# Q24_BRAKE_LIGHT.net
KiCad netlist of a schematic drawn in Altium Designer
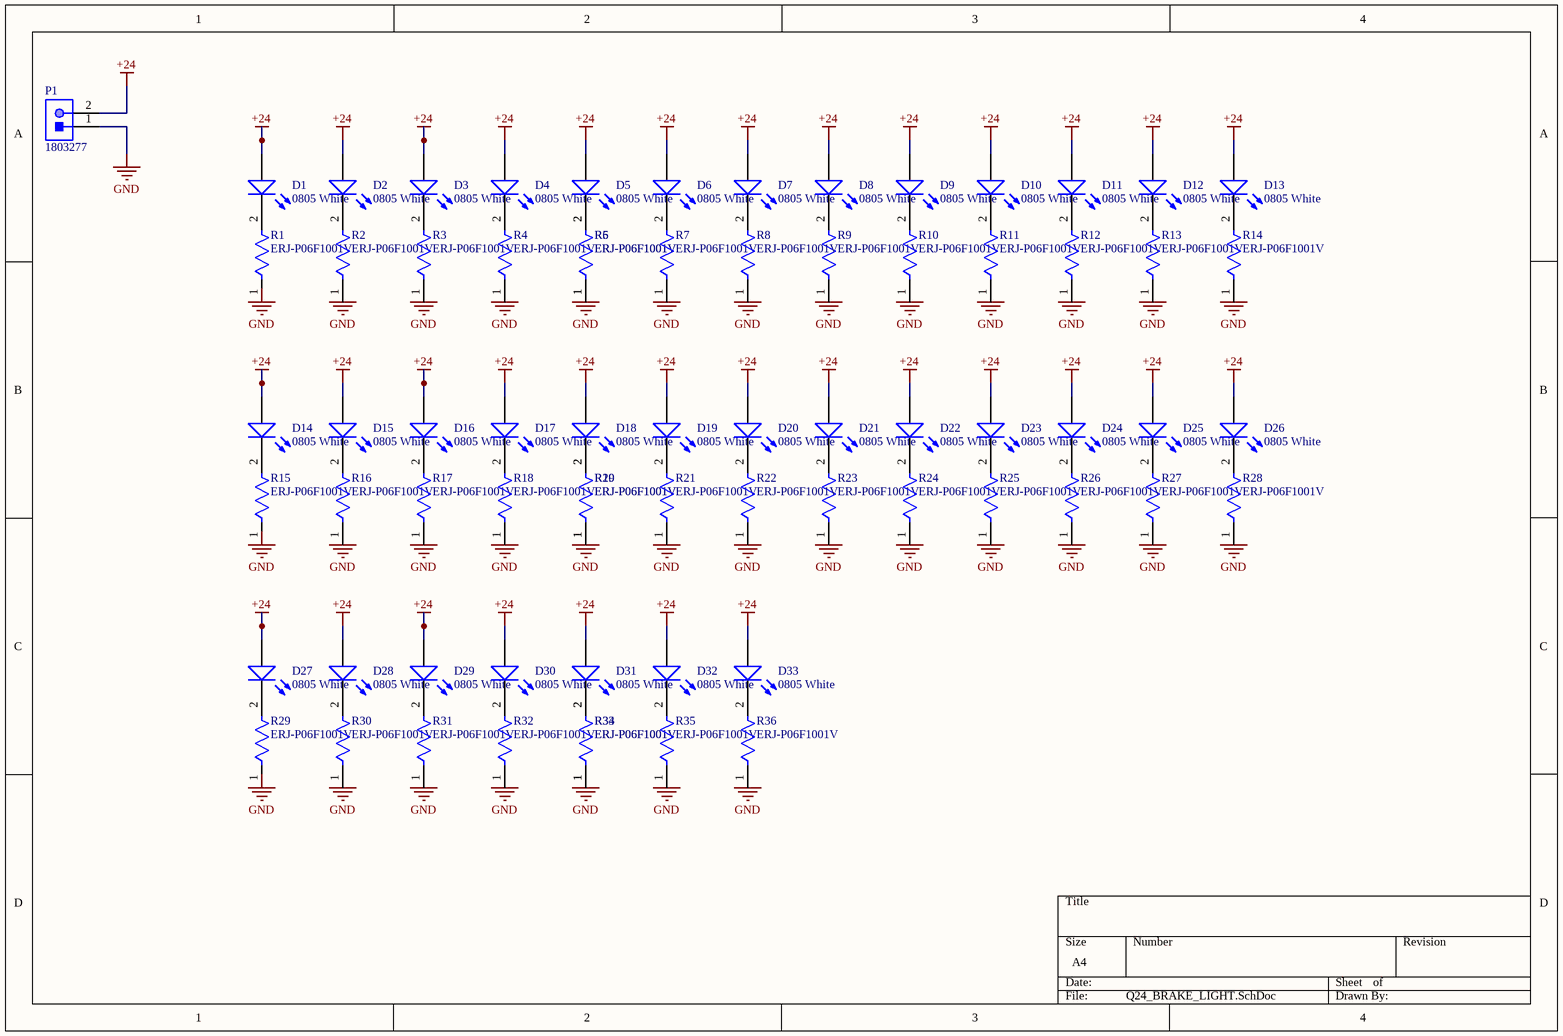
[diagram p0: Q24_BRAKE_LIGHT.SchDoc]

(export (version "E")
  (design (tool "Eeschema 10.0.6"))
  (components
    (comp (ref "D1")
      (value "0805 White")
      (footprint "0805_LED_S1")
      (description "LED")
      (libsource (lib "LED") (part "0805 LED White"))
    )
    (comp (ref "D2")
      (value "0805 White")
      (footprint "0805_LED_S1")
      (description "LED")
      (libsource (lib "LED") (part "0805 LED White"))
    )
    (comp (ref "D3")
      (value "0805 White")
      (footprint "0805_LED_S1")
      (description "LED")
      (libsource (lib "LED") (part "0805 LED White"))
    )
    (comp (ref "D4")
      (value "0805 White")
      (footprint "0805_LED_S1")
      (description "LED")
      (libsource (lib "LED") (part "0805 LED White"))
    )
    (comp (ref "D5")
      (value "0805 White")
      (footprint "0805_LED_S1")
      (description "LED")
      (libsource (lib "LED") (part "0805 LED White"))
    )
    (comp (ref "D6")
      (value "0805 White")
      (footprint "0805_LED_S1")
      (description "LED")
      (libsource (lib "LED") (part "0805 LED White"))
    )
    (comp (ref "D7")
      (value "0805 White")
      (footprint "0805_LED_S1")
      (description "LED")
      (libsource (lib "LED") (part "0805 LED White"))
    )
    (comp (ref "D8")
      (value "0805 White")
      (footprint "0805_LED_S1")
      (description "LED")
      (libsource (lib "LED") (part "0805 LED White"))
    )
    (comp (ref "D9")
      (value "0805 White")
      (footprint "0805_LED_S1")
      (description "LED")
      (libsource (lib "LED") (part "0805 LED White"))
    )
    (comp (ref "D10")
      (value "0805 White")
      (footprint "0805_LED_S1")
      (description "LED")
      (libsource (lib "LED") (part "0805 LED White"))
    )
    (comp (ref "D11")
      (value "0805 White")
      (footprint "0805_LED_S1")
      (description "LED")
      (libsource (lib "LED") (part "0805 LED White"))
    )
    (comp (ref "D12")
      (value "0805 White")
      (footprint "0805_LED_S1")
      (description "LED")
      (libsource (lib "LED") (part "0805 LED White"))
    )
    (comp (ref "D13")
      (value "0805 White")
      (footprint "0805_LED_S1")
      (description "LED")
      (libsource (lib "LED") (part "0805 LED White"))
    )
    (comp (ref "D14")
      (value "0805 White")
      (footprint "0805_LED_S1")
      (description "LED")
      (libsource (lib "LED") (part "0805 LED White"))
    )
    (comp (ref "D15")
      (value "0805 White")
      (footprint "0805_LED_S1")
      (description "LED")
      (libsource (lib "LED") (part "0805 LED White"))
    )
    (comp (ref "D16")
      (value "0805 White")
      (footprint "0805_LED_S1")
      (description "LED")
      (libsource (lib "LED") (part "0805 LED White"))
    )
    (comp (ref "D17")
      (value "0805 White")
      (footprint "0805_LED_S1")
      (description "LED")
      (libsource (lib "LED") (part "0805 LED White"))
    )
    (comp (ref "D18")
      (value "0805 White")
      (footprint "0805_LED_S1")
      (description "LED")
      (libsource (lib "LED") (part "0805 LED White"))
    )
    (comp (ref "D19")
      (value "0805 White")
      (footprint "0805_LED_S1")
      (description "LED")
      (libsource (lib "LED") (part "0805 LED White"))
    )
    (comp (ref "D20")
      (value "0805 White")
      (footprint "0805_LED_S1")
      (description "LED")
      (libsource (lib "LED") (part "0805 LED White"))
    )
    (comp (ref "D21")
      (value "0805 White")
      (footprint "0805_LED_S1")
      (description "LED")
      (libsource (lib "LED") (part "0805 LED White"))
    )
    (comp (ref "D22")
      (value "0805 White")
      (footprint "0805_LED_S1")
      (description "LED")
      (libsource (lib "LED") (part "0805 LED White"))
    )
    (comp (ref "D23")
      (value "0805 White")
      (footprint "0805_LED_S1")
      (description "LED")
      (libsource (lib "LED") (part "0805 LED White"))
    )
    (comp (ref "D24")
      (value "0805 White")
      (footprint "0805_LED_S1")
      (description "LED")
      (libsource (lib "LED") (part "0805 LED White"))
    )
    (comp (ref "D25")
      (value "0805 White")
      (footprint "0805_LED_S1")
      (description "LED")
      (libsource (lib "LED") (part "0805 LED White"))
    )
    (comp (ref "D26")
      (value "0805 White")
      (footprint "0805_LED_S1")
      (description "LED")
      (libsource (lib "LED") (part "0805 LED White"))
    )
    (comp (ref "D27")
      (value "0805 White")
      (footprint "0805_LED_S1")
      (description "LED")
      (libsource (lib "LED") (part "0805 LED White"))
    )
    (comp (ref "D28")
      (value "0805 White")
      (footprint "0805_LED_S1")
      (description "LED")
      (libsource (lib "LED") (part "0805 LED White"))
    )
    (comp (ref "D29")
      (value "0805 White")
      (footprint "0805_LED_S1")
      (description "LED")
      (libsource (lib "LED") (part "0805 LED White"))
    )
    (comp (ref "D30")
      (value "0805 White")
      (footprint "0805_LED_S1")
      (description "LED")
      (libsource (lib "LED") (part "0805 LED White"))
    )
    (comp (ref "D31")
      (value "0805 White")
      (footprint "0805_LED_S1")
      (description "LED")
      (libsource (lib "LED") (part "0805 LED White"))
    )
    (comp (ref "D32")
      (value "0805 White")
      (footprint "0805_LED_S1")
      (description "LED")
      (libsource (lib "LED") (part "0805 LED White"))
    )
    (comp (ref "D33")
      (value "0805 White")
      (footprint "0805_LED_S1")
      (description "LED")
      (libsource (lib "LED") (part "0805 LED White"))
    )
    (comp (ref "P1")
      (value "1803277")
      (footprint "PHOE-1803277_V")
      (description "Male Header, Pitch 3.81 mm, 1 x 2 Position, Height 7.25 mm, Tail Length 3.4 mm, RoHS, Bulk")
      (fields (field (name "MANUFACTURER") "Phoenix Contact"))
      (libsource (lib "Americas- FSAE- Queens University") (part "CN-1P-M-R2"))
    )
    (comp (ref "R1")
      (value "ERJ-P06F1001V")
      (footprint "FP-ERJP06-IPC_C")
      (description "RES SMD 1K OHM 1% 1/2W 0805")
      (fields (field (name "TOLERANCE") "1%"))
      (libsource (lib "Altium Content Vault") (part "1029c3af85768c4190bb7ad29bc67b5"))
    )
    (comp (ref "R2")
      (value "ERJ-P06F1001V")
      (footprint "FP-ERJP06-IPC_C")
      (description "RES SMD 1K OHM 1% 1/2W 0805")
      (fields (field (name "TOLERANCE") "1%"))
      (libsource (lib "Altium Content Vault") (part "1029c3af85768c4190bb7ad29bc67b5"))
    )
    (comp (ref "R3")
      (value "ERJ-P06F1001V")
      (footprint "FP-ERJP06-IPC_C")
      (description "RES SMD 1K OHM 1% 1/2W 0805")
      (fields (field (name "TOLERANCE") "1%"))
      (libsource (lib "Altium Content Vault") (part "1029c3af85768c4190bb7ad29bc67b5"))
    )
    (comp (ref "R4")
      (value "ERJ-P06F1001V")
      (footprint "FP-ERJP06-IPC_C")
      (description "RES SMD 1K OHM 1% 1/2W 0805")
      (fields (field (name "TOLERANCE") "1%"))
      (libsource (lib "Altium Content Vault") (part "1029c3af85768c4190bb7ad29bc67b5"))
    )
    (comp (ref "R5")
      (value "ERJ-P06F1001V")
      (footprint "FP-ERJP06-IPC_C")
      (description "RES SMD 1K OHM 1% 1/2W 0805")
      (fields (field (name "TOLERANCE") "1%"))
      (libsource (lib "Altium Content Vault") (part "1029c3af85768c4190bb7ad29bc67b5"))
    )
    (comp (ref "R6")
      (value "ERJ-P06F1001V")
      (footprint "FP-ERJP06-IPC_C")
      (description "RES SMD 1K OHM 1% 1/2W 0805")
      (fields (field (name "TOLERANCE") "1%"))
      (libsource (lib "Altium Content Vault") (part "1029c3af85768c4190bb7ad29bc67b5"))
    )
    (comp (ref "R7")
      (value "ERJ-P06F1001V")
      (footprint "FP-ERJP06-IPC_C")
      (description "RES SMD 1K OHM 1% 1/2W 0805")
      (fields (field (name "TOLERANCE") "1%"))
      (libsource (lib "Altium Content Vault") (part "1029c3af85768c4190bb7ad29bc67b5"))
    )
    (comp (ref "R8")
      (value "ERJ-P06F1001V")
      (footprint "FP-ERJP06-IPC_C")
      (description "RES SMD 1K OHM 1% 1/2W 0805")
      (fields (field (name "TOLERANCE") "1%"))
      (libsource (lib "Altium Content Vault") (part "1029c3af85768c4190bb7ad29bc67b5"))
    )
    (comp (ref "R9")
      (value "ERJ-P06F1001V")
      (footprint "FP-ERJP06-IPC_C")
      (description "RES SMD 1K OHM 1% 1/2W 0805")
      (fields (field (name "TOLERANCE") "1%"))
      (libsource (lib "Altium Content Vault") (part "1029c3af85768c4190bb7ad29bc67b5"))
    )
    (comp (ref "R10")
      (value "ERJ-P06F1001V")
      (footprint "FP-ERJP06-IPC_C")
      (description "RES SMD 1K OHM 1% 1/2W 0805")
      (fields (field (name "TOLERANCE") "1%"))
      (libsource (lib "Altium Content Vault") (part "1029c3af85768c4190bb7ad29bc67b5"))
    )
    (comp (ref "R11")
      (value "ERJ-P06F1001V")
      (footprint "FP-ERJP06-IPC_C")
      (description "RES SMD 1K OHM 1% 1/2W 0805")
      (fields (field (name "TOLERANCE") "1%"))
      (libsource (lib "Altium Content Vault") (part "1029c3af85768c4190bb7ad29bc67b5"))
    )
    (comp (ref "R12")
      (value "ERJ-P06F1001V")
      (footprint "FP-ERJP06-IPC_C")
      (description "RES SMD 1K OHM 1% 1/2W 0805")
      (fields (field (name "TOLERANCE") "1%"))
      (libsource (lib "Altium Content Vault") (part "1029c3af85768c4190bb7ad29bc67b5"))
    )
    (comp (ref "R13")
      (value "ERJ-P06F1001V")
      (footprint "FP-ERJP06-IPC_C")
      (description "RES SMD 1K OHM 1% 1/2W 0805")
      (fields (field (name "TOLERANCE") "1%"))
      (libsource (lib "Altium Content Vault") (part "1029c3af85768c4190bb7ad29bc67b5"))
    )
    (comp (ref "R14")
      (value "ERJ-P06F1001V")
      (footprint "FP-ERJP06-IPC_C")
      (description "RES SMD 1K OHM 1% 1/2W 0805")
      (fields (field (name "TOLERANCE") "1%"))
      (libsource (lib "Altium Content Vault") (part "1029c3af85768c4190bb7ad29bc67b5"))
    )
    (comp (ref "R15")
      (value "ERJ-P06F1001V")
      (footprint "FP-ERJP06-IPC_C")
      (description "RES SMD 1K OHM 1% 1/2W 0805")
      (fields (field (name "TOLERANCE") "1%"))
      (libsource (lib "Altium Content Vault") (part "1029c3af85768c4190bb7ad29bc67b5"))
    )
    (comp (ref "R16")
      (value "ERJ-P06F1001V")
      (footprint "FP-ERJP06-IPC_C")
      (description "RES SMD 1K OHM 1% 1/2W 0805")
      (fields (field (name "TOLERANCE") "1%"))
      (libsource (lib "Altium Content Vault") (part "1029c3af85768c4190bb7ad29bc67b5"))
    )
    (comp (ref "R17")
      (value "ERJ-P06F1001V")
      (footprint "FP-ERJP06-IPC_C")
      (description "RES SMD 1K OHM 1% 1/2W 0805")
      (fields (field (name "TOLERANCE") "1%"))
      (libsource (lib "Altium Content Vault") (part "1029c3af85768c4190bb7ad29bc67b5"))
    )
    (comp (ref "R18")
      (value "ERJ-P06F1001V")
      (footprint "FP-ERJP06-IPC_C")
      (description "RES SMD 1K OHM 1% 1/2W 0805")
      (fields (field (name "TOLERANCE") "1%"))
      (libsource (lib "Altium Content Vault") (part "1029c3af85768c4190bb7ad29bc67b5"))
    )
    (comp (ref "R19")
      (value "ERJ-P06F1001V")
      (footprint "FP-ERJP06-IPC_C")
      (description "RES SMD 1K OHM 1% 1/2W 0805")
      (fields (field (name "TOLERANCE") "1%"))
      (libsource (lib "Altium Content Vault") (part "1029c3af85768c4190bb7ad29bc67b5"))
    )
    (comp (ref "R20")
      (value "ERJ-P06F1001V")
      (footprint "FP-ERJP06-IPC_C")
      (description "RES SMD 1K OHM 1% 1/2W 0805")
      (fields (field (name "TOLERANCE") "1%"))
      (libsource (lib "Altium Content Vault") (part "1029c3af85768c4190bb7ad29bc67b5"))
    )
    (comp (ref "R21")
      (value "ERJ-P06F1001V")
      (footprint "FP-ERJP06-IPC_C")
      (description "RES SMD 1K OHM 1% 1/2W 0805")
      (fields (field (name "TOLERANCE") "1%"))
      (libsource (lib "Altium Content Vault") (part "1029c3af85768c4190bb7ad29bc67b5"))
    )
    (comp (ref "R22")
      (value "ERJ-P06F1001V")
      (footprint "FP-ERJP06-IPC_C")
      (description "RES SMD 1K OHM 1% 1/2W 0805")
      (fields (field (name "TOLERANCE") "1%"))
      (libsource (lib "Altium Content Vault") (part "1029c3af85768c4190bb7ad29bc67b5"))
    )
    (comp (ref "R23")
      (value "ERJ-P06F1001V")
      (footprint "FP-ERJP06-IPC_C")
      (description "RES SMD 1K OHM 1% 1/2W 0805")
      (fields (field (name "TOLERANCE") "1%"))
      (libsource (lib "Altium Content Vault") (part "1029c3af85768c4190bb7ad29bc67b5"))
    )
    (comp (ref "R24")
      (value "ERJ-P06F1001V")
      (footprint "FP-ERJP06-IPC_C")
      (description "RES SMD 1K OHM 1% 1/2W 0805")
      (fields (field (name "TOLERANCE") "1%"))
      (libsource (lib "Altium Content Vault") (part "1029c3af85768c4190bb7ad29bc67b5"))
    )
    (comp (ref "R25")
      (value "ERJ-P06F1001V")
      (footprint "FP-ERJP06-IPC_C")
      (description "RES SMD 1K OHM 1% 1/2W 0805")
      (fields (field (name "TOLERANCE") "1%"))
      (libsource (lib "Altium Content Vault") (part "1029c3af85768c4190bb7ad29bc67b5"))
    )
    (comp (ref "R26")
      (value "ERJ-P06F1001V")
      (footprint "FP-ERJP06-IPC_C")
      (description "RES SMD 1K OHM 1% 1/2W 0805")
      (fields (field (name "TOLERANCE") "1%"))
      (libsource (lib "Altium Content Vault") (part "1029c3af85768c4190bb7ad29bc67b5"))
    )
    (comp (ref "R27")
      (value "ERJ-P06F1001V")
      (footprint "FP-ERJP06-IPC_C")
      (description "RES SMD 1K OHM 1% 1/2W 0805")
      (fields (field (name "TOLERANCE") "1%"))
      (libsource (lib "Altium Content Vault") (part "1029c3af85768c4190bb7ad29bc67b5"))
    )
    (comp (ref "R28")
      (value "ERJ-P06F1001V")
      (footprint "FP-ERJP06-IPC_C")
      (description "RES SMD 1K OHM 1% 1/2W 0805")
      (fields (field (name "TOLERANCE") "1%"))
      (libsource (lib "Altium Content Vault") (part "1029c3af85768c4190bb7ad29bc67b5"))
    )
    (comp (ref "R29")
      (value "ERJ-P06F1001V")
      (footprint "FP-ERJP06-IPC_C")
      (description "RES SMD 1K OHM 1% 1/2W 0805")
      (fields (field (name "TOLERANCE") "1%"))
      (libsource (lib "Altium Content Vault") (part "1029c3af85768c4190bb7ad29bc67b5"))
    )
    (comp (ref "R30")
      (value "ERJ-P06F1001V")
      (footprint "FP-ERJP06-IPC_C")
      (description "RES SMD 1K OHM 1% 1/2W 0805")
      (fields (field (name "TOLERANCE") "1%"))
      (libsource (lib "Altium Content Vault") (part "1029c3af85768c4190bb7ad29bc67b5"))
    )
    (comp (ref "R31")
      (value "ERJ-P06F1001V")
      (footprint "FP-ERJP06-IPC_C")
      (description "RES SMD 1K OHM 1% 1/2W 0805")
      (fields (field (name "TOLERANCE") "1%"))
      (libsource (lib "Altium Content Vault") (part "1029c3af85768c4190bb7ad29bc67b5"))
    )
    (comp (ref "R32")
      (value "ERJ-P06F1001V")
      (footprint "FP-ERJP06-IPC_C")
      (description "RES SMD 1K OHM 1% 1/2W 0805")
      (fields (field (name "TOLERANCE") "1%"))
      (libsource (lib "Altium Content Vault") (part "1029c3af85768c4190bb7ad29bc67b5"))
    )
    (comp (ref "R33")
      (value "ERJ-P06F1001V")
      (footprint "FP-ERJP06-IPC_C")
      (description "RES SMD 1K OHM 1% 1/2W 0805")
      (fields (field (name "TOLERANCE") "1%"))
      (libsource (lib "Altium Content Vault") (part "1029c3af85768c4190bb7ad29bc67b5"))
    )
    (comp (ref "R34")
      (value "ERJ-P06F1001V")
      (footprint "FP-ERJP06-IPC_C")
      (description "RES SMD 1K OHM 1% 1/2W 0805")
      (fields (field (name "TOLERANCE") "1%"))
      (libsource (lib "Altium Content Vault") (part "1029c3af85768c4190bb7ad29bc67b5"))
    )
    (comp (ref "R35")
      (value "ERJ-P06F1001V")
      (footprint "FP-ERJP06-IPC_C")
      (description "RES SMD 1K OHM 1% 1/2W 0805")
      (fields (field (name "TOLERANCE") "1%"))
      (libsource (lib "Altium Content Vault") (part "1029c3af85768c4190bb7ad29bc67b5"))
    )
    (comp (ref "R36")
      (value "ERJ-P06F1001V")
      (footprint "FP-ERJP06-IPC_C")
      (description "RES SMD 1K OHM 1% 1/2W 0805")
      (fields (field (name "TOLERANCE") "1%"))
      (libsource (lib "Altium Content Vault") (part "1029c3af85768c4190bb7ad29bc67b5"))
    )
  )
  (nets
    (net (code "1") (name "+24") (class "Default")
      (node (ref "D1") (pin "A") (pinfunction "A_A") (pintype "passive"))
      (node (ref "D10") (pin "A") (pinfunction "A_A") (pintype "passive"))
      (node (ref "D11") (pin "A") (pinfunction "A_A") (pintype "passive"))
      (node (ref "D12") (pin "A") (pinfunction "A_A") (pintype "passive"))
      (node (ref "D13") (pin "A") (pinfunction "A_A") (pintype "passive"))
      (node (ref "D14") (pin "A") (pinfunction "A_A") (pintype "passive"))
      (node (ref "D15") (pin "A") (pinfunction "A_A") (pintype "passive"))
      (node (ref "D16") (pin "A") (pinfunction "A_A") (pintype "passive"))
      (node (ref "D17") (pin "A") (pinfunction "A_A") (pintype "passive"))
      (node (ref "D18") (pin "A") (pinfunction "A_A") (pintype "passive"))
      (node (ref "D19") (pin "A") (pinfunction "A_A") (pintype "passive"))
      (node (ref "D2") (pin "A") (pinfunction "A_A") (pintype "passive"))
      (node (ref "D20") (pin "A") (pinfunction "A_A") (pintype "passive"))
      (node (ref "D21") (pin "A") (pinfunction "A_A") (pintype "passive"))
      (node (ref "D22") (pin "A") (pinfunction "A_A") (pintype "passive"))
      (node (ref "D23") (pin "A") (pinfunction "A_A") (pintype "passive"))
      (node (ref "D24") (pin "A") (pinfunction "A_A") (pintype "passive"))
      (node (ref "D25") (pin "A") (pinfunction "A_A") (pintype "passive"))
      (node (ref "D26") (pin "A") (pinfunction "A_A") (pintype "passive"))
      (node (ref "D27") (pin "A") (pinfunction "A_A") (pintype "passive"))
      (node (ref "D28") (pin "A") (pinfunction "A_A") (pintype "passive"))
      (node (ref "D29") (pin "A") (pinfunction "A_A") (pintype "passive"))
      (node (ref "D3") (pin "A") (pinfunction "A_A") (pintype "passive"))
      (node (ref "D30") (pin "A") (pinfunction "A_A") (pintype "passive"))
      (node (ref "D31") (pin "A") (pinfunction "A_A") (pintype "passive"))
      (node (ref "D32") (pin "A") (pinfunction "A_A") (pintype "passive"))
      (node (ref "D33") (pin "A") (pinfunction "A_A") (pintype "passive"))
      (node (ref "D4") (pin "A") (pinfunction "A_A") (pintype "passive"))
      (node (ref "D5") (pin "A") (pinfunction "A_A") (pintype "passive"))
      (node (ref "D6") (pin "A") (pinfunction "A_A") (pintype "passive"))
      (node (ref "D7") (pin "A") (pinfunction "A_A") (pintype "passive"))
      (node (ref "D8") (pin "A") (pinfunction "A_A") (pintype "passive"))
      (node (ref "D9") (pin "A") (pinfunction "A_A") (pintype "passive"))
      (node (ref "P1") (pin "2") (pinfunction "2_2") (pintype "passive"))
    )
    (net (code "2") (name "GND") (class "Default")
      (node (ref "P1") (pin "1") (pinfunction "1_1") (pintype "passive"))
    )
    (net (code "3") (name "Net-(R5-Pad1)") (class "Default")
      (node (ref "R5") (pin "1") (pinfunction "1_1") (pintype "passive"))
      (node (ref "R6") (pin "1") (pinfunction "1_1") (pintype "passive"))
    )
    (net (code "4") (name "Net-(R5-Pad2)") (class "Default")
      (node (ref "R5") (pin "2") (pinfunction "2_2") (pintype "passive"))
      (node (ref "R6") (pin "2") (pinfunction "2_2") (pintype "passive"))
    )
    (net (code "5") (name "Net-(R19-Pad1)") (class "Default")
      (node (ref "R19") (pin "1") (pinfunction "1_1") (pintype "passive"))
      (node (ref "R20") (pin "1") (pinfunction "1_1") (pintype "passive"))
    )
    (net (code "6") (name "Net-(R19-Pad2)") (class "Default")
      (node (ref "R19") (pin "2") (pinfunction "2_2") (pintype "passive"))
      (node (ref "R20") (pin "2") (pinfunction "2_2") (pintype "passive"))
    )
    (net (code "7") (name "Net-(R33-Pad1)") (class "Default")
      (node (ref "R33") (pin "1") (pinfunction "1_1") (pintype "passive"))
      (node (ref "R34") (pin "1") (pinfunction "1_1") (pintype "passive"))
    )
    (net (code "8") (name "Net-(R33-Pad2)") (class "Default")
      (node (ref "R33") (pin "2") (pinfunction "2_2") (pintype "passive"))
      (node (ref "R34") (pin "2") (pinfunction "2_2") (pintype "passive"))
    )
    (net (code "9") (name "unconnected-(D1-PadK)") (class "Default")
      (node (ref "D1") (pin "K") (pinfunction "K_K") (pintype "passive"))
    )
    (net (code "10") (name "unconnected-(D2-PadK)") (class "Default")
      (node (ref "D2") (pin "K") (pinfunction "K_K") (pintype "passive"))
    )
    (net (code "11") (name "unconnected-(D3-PadK)") (class "Default")
      (node (ref "D3") (pin "K") (pinfunction "K_K") (pintype "passive"))
    )
    (net (code "12") (name "unconnected-(D4-PadK)") (class "Default")
      (node (ref "D4") (pin "K") (pinfunction "K_K") (pintype "passive"))
    )
    (net (code "13") (name "unconnected-(D5-PadK)") (class "Default")
      (node (ref "D5") (pin "K") (pinfunction "K_K") (pintype "passive"))
    )
    (net (code "14") (name "unconnected-(D6-PadK)") (class "Default")
      (node (ref "D6") (pin "K") (pinfunction "K_K") (pintype "passive"))
    )
    (net (code "15") (name "unconnected-(D7-PadK)") (class "Default")
      (node (ref "D7") (pin "K") (pinfunction "K_K") (pintype "passive"))
    )
    (net (code "16") (name "unconnected-(D8-PadK)") (class "Default")
      (node (ref "D8") (pin "K") (pinfunction "K_K") (pintype "passive"))
    )
    (net (code "17") (name "unconnected-(D9-PadK)") (class "Default")
      (node (ref "D9") (pin "K") (pinfunction "K_K") (pintype "passive"))
    )
    (net (code "18") (name "unconnected-(D10-PadK)") (class "Default")
      (node (ref "D10") (pin "K") (pinfunction "K_K") (pintype "passive"))
    )
    (net (code "19") (name "unconnected-(D11-PadK)") (class "Default")
      (node (ref "D11") (pin "K") (pinfunction "K_K") (pintype "passive"))
    )
    (net (code "20") (name "unconnected-(D12-PadK)") (class "Default")
      (node (ref "D12") (pin "K") (pinfunction "K_K") (pintype "passive"))
    )
    (net (code "21") (name "unconnected-(D13-PadK)") (class "Default")
      (node (ref "D13") (pin "K") (pinfunction "K_K") (pintype "passive"))
    )
    (net (code "22") (name "unconnected-(D14-PadK)") (class "Default")
      (node (ref "D14") (pin "K") (pinfunction "K_K") (pintype "passive"))
    )
    (net (code "23") (name "unconnected-(D15-PadK)") (class "Default")
      (node (ref "D15") (pin "K") (pinfunction "K_K") (pintype "passive"))
    )
    (net (code "24") (name "unconnected-(D16-PadK)") (class "Default")
      (node (ref "D16") (pin "K") (pinfunction "K_K") (pintype "passive"))
    )
    (net (code "25") (name "unconnected-(D17-PadK)") (class "Default")
      (node (ref "D17") (pin "K") (pinfunction "K_K") (pintype "passive"))
    )
    (net (code "26") (name "unconnected-(D18-PadK)") (class "Default")
      (node (ref "D18") (pin "K") (pinfunction "K_K") (pintype "passive"))
    )
    (net (code "27") (name "unconnected-(D19-PadK)") (class "Default")
      (node (ref "D19") (pin "K") (pinfunction "K_K") (pintype "passive"))
    )
    (net (code "28") (name "unconnected-(D20-PadK)") (class "Default")
      (node (ref "D20") (pin "K") (pinfunction "K_K") (pintype "passive"))
    )
    (net (code "29") (name "unconnected-(D21-PadK)") (class "Default")
      (node (ref "D21") (pin "K") (pinfunction "K_K") (pintype "passive"))
    )
    (net (code "30") (name "unconnected-(D22-PadK)") (class "Default")
      (node (ref "D22") (pin "K") (pinfunction "K_K") (pintype "passive"))
    )
    (net (code "31") (name "unconnected-(D23-PadK)") (class "Default")
      (node (ref "D23") (pin "K") (pinfunction "K_K") (pintype "passive"))
    )
    (net (code "32") (name "unconnected-(D24-PadK)") (class "Default")
      (node (ref "D24") (pin "K") (pinfunction "K_K") (pintype "passive"))
    )
    (net (code "33") (name "unconnected-(D25-PadK)") (class "Default")
      (node (ref "D25") (pin "K") (pinfunction "K_K") (pintype "passive"))
    )
    (net (code "34") (name "unconnected-(D26-PadK)") (class "Default")
      (node (ref "D26") (pin "K") (pinfunction "K_K") (pintype "passive"))
    )
    (net (code "35") (name "unconnected-(D27-PadK)") (class "Default")
      (node (ref "D27") (pin "K") (pinfunction "K_K") (pintype "passive"))
    )
    (net (code "36") (name "unconnected-(D28-PadK)") (class "Default")
      (node (ref "D28") (pin "K") (pinfunction "K_K") (pintype "passive"))
    )
    (net (code "37") (name "unconnected-(D29-PadK)") (class "Default")
      (node (ref "D29") (pin "K") (pinfunction "K_K") (pintype "passive"))
    )
    (net (code "38") (name "unconnected-(D30-PadK)") (class "Default")
      (node (ref "D30") (pin "K") (pinfunction "K_K") (pintype "passive"))
    )
    (net (code "39") (name "unconnected-(D31-PadK)") (class "Default")
      (node (ref "D31") (pin "K") (pinfunction "K_K") (pintype "passive"))
    )
    (net (code "40") (name "unconnected-(D32-PadK)") (class "Default")
      (node (ref "D32") (pin "K") (pinfunction "K_K") (pintype "passive"))
    )
    (net (code "41") (name "unconnected-(D33-PadK)") (class "Default")
      (node (ref "D33") (pin "K") (pinfunction "K_K") (pintype "passive"))
    )
    (net (code "42") (name "unconnected-(R1-Pad1)") (class "Default")
      (node (ref "R1") (pin "1") (pinfunction "1_1") (pintype "passive"))
    )
    (net (code "43") (name "unconnected-(R1-Pad2)") (class "Default")
      (node (ref "R1") (pin "2") (pinfunction "2_2") (pintype "passive"))
    )
    (net (code "44") (name "unconnected-(R2-Pad1)") (class "Default")
      (node (ref "R2") (pin "1") (pinfunction "1_1") (pintype "passive"))
    )
    (net (code "45") (name "unconnected-(R2-Pad2)") (class "Default")
      (node (ref "R2") (pin "2") (pinfunction "2_2") (pintype "passive"))
    )
    (net (code "46") (name "unconnected-(R3-Pad1)") (class "Default")
      (node (ref "R3") (pin "1") (pinfunction "1_1") (pintype "passive"))
    )
    (net (code "47") (name "unconnected-(R3-Pad2)") (class "Default")
      (node (ref "R3") (pin "2") (pinfunction "2_2") (pintype "passive"))
    )
    (net (code "48") (name "unconnected-(R4-Pad1)") (class "Default")
      (node (ref "R4") (pin "1") (pinfunction "1_1") (pintype "passive"))
    )
    (net (code "49") (name "unconnected-(R4-Pad2)") (class "Default")
      (node (ref "R4") (pin "2") (pinfunction "2_2") (pintype "passive"))
    )
    (net (code "50") (name "unconnected-(R7-Pad1)") (class "Default")
      (node (ref "R7") (pin "1") (pinfunction "1_1") (pintype "passive"))
    )
    (net (code "51") (name "unconnected-(R7-Pad2)") (class "Default")
      (node (ref "R7") (pin "2") (pinfunction "2_2") (pintype "passive"))
    )
    (net (code "52") (name "unconnected-(R8-Pad1)") (class "Default")
      (node (ref "R8") (pin "1") (pinfunction "1_1") (pintype "passive"))
    )
    (net (code "53") (name "unconnected-(R8-Pad2)") (class "Default")
      (node (ref "R8") (pin "2") (pinfunction "2_2") (pintype "passive"))
    )
    (net (code "54") (name "unconnected-(R9-Pad1)") (class "Default")
      (node (ref "R9") (pin "1") (pinfunction "1_1") (pintype "passive"))
    )
    (net (code "55") (name "unconnected-(R9-Pad2)") (class "Default")
      (node (ref "R9") (pin "2") (pinfunction "2_2") (pintype "passive"))
    )
    (net (code "56") (name "unconnected-(R10-Pad1)") (class "Default")
      (node (ref "R10") (pin "1") (pinfunction "1_1") (pintype "passive"))
    )
    (net (code "57") (name "unconnected-(R10-Pad2)") (class "Default")
      (node (ref "R10") (pin "2") (pinfunction "2_2") (pintype "passive"))
    )
    (net (code "58") (name "unconnected-(R11-Pad1)") (class "Default")
      (node (ref "R11") (pin "1") (pinfunction "1_1") (pintype "passive"))
    )
    (net (code "59") (name "unconnected-(R11-Pad2)") (class "Default")
      (node (ref "R11") (pin "2") (pinfunction "2_2") (pintype "passive"))
    )
    (net (code "60") (name "unconnected-(R12-Pad1)") (class "Default")
      (node (ref "R12") (pin "1") (pinfunction "1_1") (pintype "passive"))
    )
    (net (code "61") (name "unconnected-(R12-Pad2)") (class "Default")
      (node (ref "R12") (pin "2") (pinfunction "2_2") (pintype "passive"))
    )
    (net (code "62") (name "unconnected-(R13-Pad1)") (class "Default")
      (node (ref "R13") (pin "1") (pinfunction "1_1") (pintype "passive"))
    )
    (net (code "63") (name "unconnected-(R13-Pad2)") (class "Default")
      (node (ref "R13") (pin "2") (pinfunction "2_2") (pintype "passive"))
    )
    (net (code "64") (name "unconnected-(R14-Pad1)") (class "Default")
      (node (ref "R14") (pin "1") (pinfunction "1_1") (pintype "passive"))
    )
    (net (code "65") (name "unconnected-(R14-Pad2)") (class "Default")
      (node (ref "R14") (pin "2") (pinfunction "2_2") (pintype "passive"))
    )
    (net (code "66") (name "unconnected-(R15-Pad1)") (class "Default")
      (node (ref "R15") (pin "1") (pinfunction "1_1") (pintype "passive"))
    )
    (net (code "67") (name "unconnected-(R15-Pad2)") (class "Default")
      (node (ref "R15") (pin "2") (pinfunction "2_2") (pintype "passive"))
    )
    (net (code "68") (name "unconnected-(R16-Pad1)") (class "Default")
      (node (ref "R16") (pin "1") (pinfunction "1_1") (pintype "passive"))
    )
    (net (code "69") (name "unconnected-(R16-Pad2)") (class "Default")
      (node (ref "R16") (pin "2") (pinfunction "2_2") (pintype "passive"))
    )
    (net (code "70") (name "unconnected-(R17-Pad1)") (class "Default")
      (node (ref "R17") (pin "1") (pinfunction "1_1") (pintype "passive"))
    )
    (net (code "71") (name "unconnected-(R17-Pad2)") (class "Default")
      (node (ref "R17") (pin "2") (pinfunction "2_2") (pintype "passive"))
    )
    (net (code "72") (name "unconnected-(R18-Pad1)") (class "Default")
      (node (ref "R18") (pin "1") (pinfunction "1_1") (pintype "passive"))
    )
    (net (code "73") (name "unconnected-(R18-Pad2)") (class "Default")
      (node (ref "R18") (pin "2") (pinfunction "2_2") (pintype "passive"))
    )
    (net (code "74") (name "unconnected-(R21-Pad1)") (class "Default")
      (node (ref "R21") (pin "1") (pinfunction "1_1") (pintype "passive"))
    )
    (net (code "75") (name "unconnected-(R21-Pad2)") (class "Default")
      (node (ref "R21") (pin "2") (pinfunction "2_2") (pintype "passive"))
    )
    (net (code "76") (name "unconnected-(R22-Pad1)") (class "Default")
      (node (ref "R22") (pin "1") (pinfunction "1_1") (pintype "passive"))
    )
    (net (code "77") (name "unconnected-(R22-Pad2)") (class "Default")
      (node (ref "R22") (pin "2") (pinfunction "2_2") (pintype "passive"))
    )
    (net (code "78") (name "unconnected-(R23-Pad1)") (class "Default")
      (node (ref "R23") (pin "1") (pinfunction "1_1") (pintype "passive"))
    )
    (net (code "79") (name "unconnected-(R23-Pad2)") (class "Default")
      (node (ref "R23") (pin "2") (pinfunction "2_2") (pintype "passive"))
    )
    (net (code "80") (name "unconnected-(R24-Pad1)") (class "Default")
      (node (ref "R24") (pin "1") (pinfunction "1_1") (pintype "passive"))
    )
    (net (code "81") (name "unconnected-(R24-Pad2)") (class "Default")
      (node (ref "R24") (pin "2") (pinfunction "2_2") (pintype "passive"))
    )
    (net (code "82") (name "unconnected-(R25-Pad1)") (class "Default")
      (node (ref "R25") (pin "1") (pinfunction "1_1") (pintype "passive"))
    )
    (net (code "83") (name "unconnected-(R25-Pad2)") (class "Default")
      (node (ref "R25") (pin "2") (pinfunction "2_2") (pintype "passive"))
    )
    (net (code "84") (name "unconnected-(R26-Pad1)") (class "Default")
      (node (ref "R26") (pin "1") (pinfunction "1_1") (pintype "passive"))
    )
    (net (code "85") (name "unconnected-(R26-Pad2)") (class "Default")
      (node (ref "R26") (pin "2") (pinfunction "2_2") (pintype "passive"))
    )
    (net (code "86") (name "unconnected-(R27-Pad1)") (class "Default")
      (node (ref "R27") (pin "1") (pinfunction "1_1") (pintype "passive"))
    )
    (net (code "87") (name "unconnected-(R27-Pad2)") (class "Default")
      (node (ref "R27") (pin "2") (pinfunction "2_2") (pintype "passive"))
    )
    (net (code "88") (name "unconnected-(R28-Pad1)") (class "Default")
      (node (ref "R28") (pin "1") (pinfunction "1_1") (pintype "passive"))
    )
    (net (code "89") (name "unconnected-(R28-Pad2)") (class "Default")
      (node (ref "R28") (pin "2") (pinfunction "2_2") (pintype "passive"))
    )
    (net (code "90") (name "unconnected-(R29-Pad1)") (class "Default")
      (node (ref "R29") (pin "1") (pinfunction "1_1") (pintype "passive"))
    )
    (net (code "91") (name "unconnected-(R29-Pad2)") (class "Default")
      (node (ref "R29") (pin "2") (pinfunction "2_2") (pintype "passive"))
    )
    (net (code "92") (name "unconnected-(R30-Pad1)") (class "Default")
      (node (ref "R30") (pin "1") (pinfunction "1_1") (pintype "passive"))
    )
    (net (code "93") (name "unconnected-(R30-Pad2)") (class "Default")
      (node (ref "R30") (pin "2") (pinfunction "2_2") (pintype "passive"))
    )
    (net (code "94") (name "unconnected-(R31-Pad1)") (class "Default")
      (node (ref "R31") (pin "1") (pinfunction "1_1") (pintype "passive"))
    )
    (net (code "95") (name "unconnected-(R31-Pad2)") (class "Default")
      (node (ref "R31") (pin "2") (pinfunction "2_2") (pintype "passive"))
    )
    (net (code "96") (name "unconnected-(R32-Pad1)") (class "Default")
      (node (ref "R32") (pin "1") (pinfunction "1_1") (pintype "passive"))
    )
    (net (code "97") (name "unconnected-(R32-Pad2)") (class "Default")
      (node (ref "R32") (pin "2") (pinfunction "2_2") (pintype "passive"))
    )
    (net (code "98") (name "unconnected-(R35-Pad1)") (class "Default")
      (node (ref "R35") (pin "1") (pinfunction "1_1") (pintype "passive"))
    )
    (net (code "99") (name "unconnected-(R35-Pad2)") (class "Default")
      (node (ref "R35") (pin "2") (pinfunction "2_2") (pintype "passive"))
    )
    (net (code "100") (name "unconnected-(R36-Pad1)") (class "Default")
      (node (ref "R36") (pin "1") (pinfunction "1_1") (pintype "passive"))
    )
    (net (code "101") (name "unconnected-(R36-Pad2)") (class "Default")
      (node (ref "R36") (pin "2") (pinfunction "2_2") (pintype "passive"))
    )
  )
)
